# TCA_CLK_DIST_V2_4.net
KiCad netlist of a schematic drawn in Altium Designer
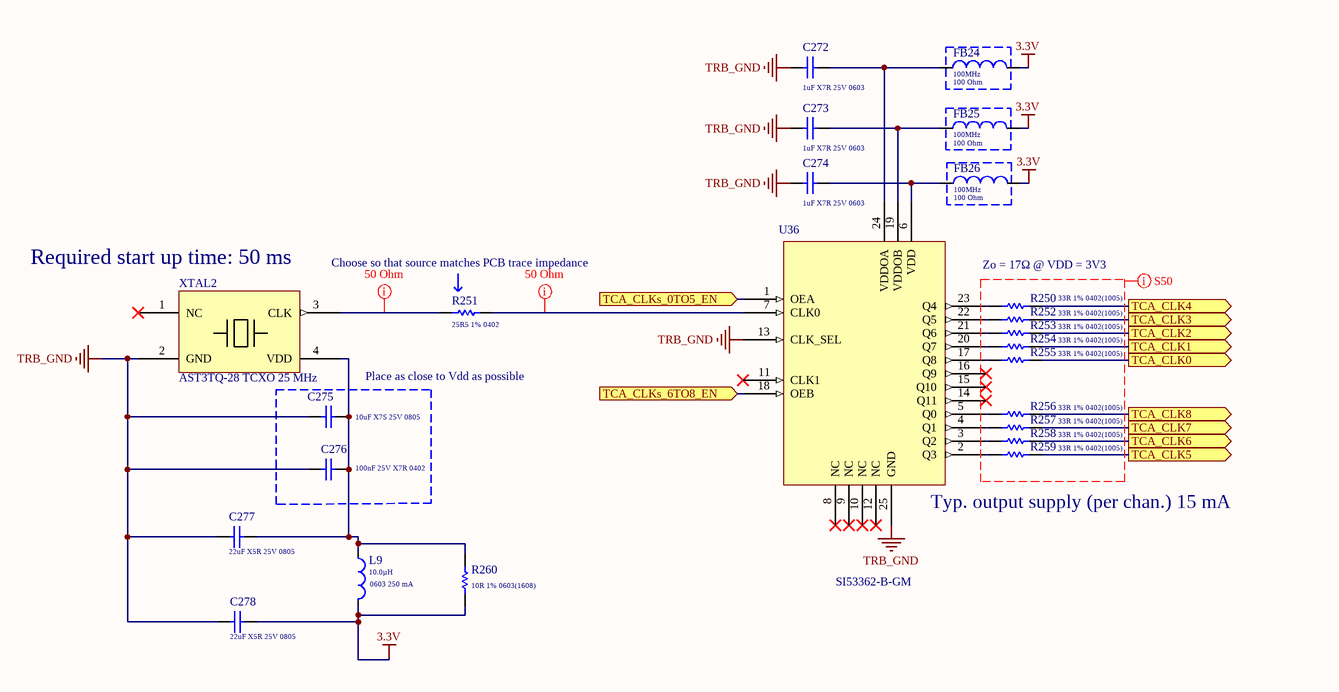
[diagram p0: TCA_CLK_DIST_V2_4.SchDoc]

(export (version "E")
  (design (tool "Eeschema 10.0.6"))
  (components
    (comp (ref "C272")
      (value "Cap_Murata_GCJ188R71E105KA01J_1uF")
      (footprint "Cap_Murata_GCJ188R71E105KA01J_1uF")
      (description "CAP CER 1uF 25V X7R 0603")
      (fields (field (name "CAPACITANCE") "1uF X7R 25V 0603"))
      (libsource (lib "Cap_Murata_GCJ188R71E105KA01J_1uF") (part "Cap_Murata_GCJ188R71E105KA01J_1uF"))
    )
    (comp (ref "C273")
      (value "Cap_Murata_GCJ188R71E105KA01J_1uF")
      (footprint "Cap_Murata_GCJ188R71E105KA01J_1uF")
      (description "CAP CER 1uF 25V X7R 0603")
      (fields (field (name "CAPACITANCE") "1uF X7R 25V 0603"))
      (libsource (lib "Cap_Murata_GCJ188R71E105KA01J_1uF") (part "Cap_Murata_GCJ188R71E105KA01J_1uF"))
    )
    (comp (ref "C274")
      (value "Cap_Murata_GCJ188R71E105KA01J_1uF")
      (footprint "Cap_Murata_GCJ188R71E105KA01J_1uF")
      (description "CAP CER 1uF 25V X7R 0603")
      (fields (field (name "CAPACITANCE") "1uF X7R 25V 0603"))
      (libsource (lib "Cap_Murata_GCJ188R71E105KA01J_1uF") (part "Cap_Murata_GCJ188R71E105KA01J_1uF"))
    )
    (comp (ref "C275")
      (value "Cap_Murata_ GRM21BC71E106ME11L_10uF")
      (footprint "Cap_Murata_ GRM21BC71E106ME11L_10uF")
      (description "CAP CER 10uF 25V X7R 0805")
      (fields (field (name "CAPACITANCE") "10uF X7S 25V 0805"))
      (libsource (lib "Cap_Murata_ GRM21BC71E106ME11L_10uF") (part "Cap_Murata_ GRM21BC71E106ME11L_10uF"))
    )
    (comp (ref "C276")
      (value "Cap_Taiyo_Yuden_TMK105B7104KV-FR_100nF")
      (footprint "Cap_Taiyo_Yuden_TMK105B7104KV-FR_100nF")
      (description "CAP CER 100nF 25V X7R 0402")
      (fields (field (name "CAPACITANCE") "100nF 25V X7R 0402"))
      (libsource (lib "Cap_Taiyo_Yuden_TMK105B7104KV-FR_100nF") (part "Cap_Taiyo_Yuden_TMK105B7104KV-FR_100nF"))
    )
    (comp (ref "C277")
      (value "Cap_Murata_GRT21BR61E226ME13L_22uF")
      (footprint "Cap_Murata_GRT21BR61E226ME13L_22uF")
      (description "CAP CER 22uF 25V X5R 0805")
      (fields (field (name "CAPACITANCE") "22uF X5R 25V 0805"))
      (libsource (lib "Cap_Murata_GRT21BR61E226ME13L_22uF") (part "Cap_Murata_GRT21BR61E226ME13L_22uF"))
    )
    (comp (ref "C278")
      (value "Cap_Murata_GRT21BR61E226ME13L_22uF")
      (footprint "Cap_Murata_GRT21BR61E226ME13L_22uF")
      (description "CAP CER 22uF 25V X5R 0805")
      (fields (field (name "CAPACITANCE") "22uF X5R 25V 0805"))
      (libsource (lib "Cap_Murata_GRT21BR61E226ME13L_22uF") (part "Cap_Murata_GRT21BR61E226ME13L_22uF"))
    )
    (comp (ref "FB24")
      (value "742792731")
      (footprint "FB_Wurth_Electronics_742792731_100Ohms")
      (description "FB SMD 100 OHM 25% 1.2A 0402")
      (fields (field (name "MEASURING FREQUENCY") "100MHz") (field (name "IMPEDANCE") "100 Ohm"))
      (libsource (lib "FB_Wurth_Electronics_742792731_100Ohms") (part "FB_Wurth_Electronics_742792731_100Ohms"))
    )
    (comp (ref "FB25")
      (value "742792731")
      (footprint "FB_Wurth_Electronics_742792731_100Ohms")
      (description "FB SMD 100 OHM 25% 1.2A 0402")
      (fields (field (name "MEASURING FREQUENCY") "100MHz") (field (name "IMPEDANCE") "100 Ohm"))
      (libsource (lib "FB_Wurth_Electronics_742792731_100Ohms") (part "FB_Wurth_Electronics_742792731_100Ohms"))
    )
    (comp (ref "FB26")
      (value "742792731")
      (footprint "FB_Wurth_Electronics_742792731_100Ohms")
      (description "FB SMD 100 OHM 25% 1.2A 0402")
      (fields (field (name "MEASURING FREQUENCY") "100MHz") (field (name "IMPEDANCE") "100 Ohm"))
      (libsource (lib "FB_Wurth_Electronics_742792731_100Ohms") (part "FB_Wurth_Electronics_742792731_100Ohms"))
    )
    (comp (ref "L9")
      (value "0603 250 mA")
      (footprint "TDK_MLZ1608M100WT_0")
      (description "IND 10µH Shielded Multilayer Inductor 250mA 1.365 Ohm Max 0603 (1608 Metric)")
      (fields
        (field (name "PART NUMBER") "MLZ1608M100WT")
        (field (name "MANUFACTURER") "TDK")
        (field (name "INDUCTANCE") "10.0µH")
      )
      (libsource (lib "Ind_TDK_MLZ1608M100WT_10uH") (part "Ind_TDK_MLZ1608M100WT_eec"))
    )
    (comp (ref "R250")
      (value "33R 1% 0402(1005)")
      (footprint "RESC0402(1005)_L")
      (description "33R 0.063W 1% 0402 (1005 Metric)  SMD")
      (fields (field (name "TOLERANCE") "1 %") (field (name "POWER") "0.063 W"))
      (libsource (lib "Altium Content Vault") (part "RES"))
    )
    (comp (ref "R251")
      (value "25R5 1% 0402")
      (footprint "RESC0402(1005)_L")
      (description "25R5 0.063W 1% 0402 (1005 Metric)  SMD")
      (fields (field (name "TOLERANCE") "1 %") (field (name "POWER") "0.063 W"))
      (libsource (lib "Altium Content Vault") (part "RES"))
    )
    (comp (ref "R252")
      (value "33R 1% 0402(1005)")
      (footprint "RESC0402(1005)_L")
      (description "33R 0.063W 1% 0402 (1005 Metric)  SMD")
      (fields (field (name "TOLERANCE") "1 %") (field (name "POWER") "0.063 W"))
      (libsource (lib "Altium Content Vault") (part "RES"))
    )
    (comp (ref "R253")
      (value "33R 1% 0402(1005)")
      (footprint "RESC0402(1005)_L")
      (description "33R 0.063W 1% 0402 (1005 Metric)  SMD")
      (fields (field (name "TOLERANCE") "1 %") (field (name "POWER") "0.063 W"))
      (libsource (lib "Altium Content Vault") (part "RES"))
    )
    (comp (ref "R254")
      (value "33R 1% 0402(1005)")
      (footprint "RESC0402(1005)_L")
      (description "33R 0.063W 1% 0402 (1005 Metric)  SMD")
      (fields (field (name "TOLERANCE") "1 %") (field (name "POWER") "0.063 W"))
      (libsource (lib "Altium Content Vault") (part "RES"))
    )
    (comp (ref "R255")
      (value "33R 1% 0402(1005)")
      (footprint "RESC0402(1005)_L")
      (description "33R 0.063W 1% 0402 (1005 Metric)  SMD")
      (fields (field (name "TOLERANCE") "1 %") (field (name "POWER") "0.063 W"))
      (libsource (lib "Altium Content Vault") (part "RES"))
    )
    (comp (ref "R256")
      (value "33R 1% 0402(1005)")
      (footprint "RESC0402(1005)_L")
      (description "33R 0.063W 1% 0402 (1005 Metric)  SMD")
      (fields (field (name "TOLERANCE") "1 %") (field (name "POWER") "0.063 W"))
      (libsource (lib "Altium Content Vault") (part "RES"))
    )
    (comp (ref "R257")
      (value "33R 1% 0402(1005)")
      (footprint "RESC0402(1005)_L")
      (description "33R 0.063W 1% 0402 (1005 Metric)  SMD")
      (fields (field (name "TOLERANCE") "1 %") (field (name "POWER") "0.063 W"))
      (libsource (lib "Altium Content Vault") (part "RES"))
    )
    (comp (ref "R258")
      (value "33R 1% 0402(1005)")
      (footprint "RESC0402(1005)_L")
      (description "33R 0.063W 1% 0402 (1005 Metric)  SMD")
      (fields (field (name "TOLERANCE") "1 %") (field (name "POWER") "0.063 W"))
      (libsource (lib "Altium Content Vault") (part "RES"))
    )
    (comp (ref "R259")
      (value "33R 1% 0402(1005)")
      (footprint "RESC0402(1005)_L")
      (description "33R 0.063W 1% 0402 (1005 Metric)  SMD")
      (fields (field (name "TOLERANCE") "1 %") (field (name "POWER") "0.063 W"))
      (libsource (lib "Altium Content Vault") (part "RES"))
    )
    (comp (ref "R260")
      (value "10R 1% 0603(1608)")
      (footprint "RESC0603(1608)_L")
      (description "10R 0.1W 1% 0603 (1608 Metric)  SMD")
      (fields (field (name "TOLERANCE") "1 %") (field (name "POWER") "0.1 W"))
      (libsource (lib "Altium Content Vault") (part "RES"))
    )
    (comp (ref "U36")
      (value "SI53362-B-GM")
      (footprint "Si53362")
      (description "Clock Buffer LVCMOS 2:12 buffer (200MHz), 2:1 LVCMOS input max, output enable (QFN24)")
      (libsource (lib "SI53362") (part "SI53362-B-GM"))
    )
    (comp (ref "XTAL2")
      (value "AST3TQ-28 TCXO 25 MHz")
      (footprint "XTAL_ASDM1-25.000MHZ-LC-T")
      (description "TCXO Oscillators 25MHz 3.3Volt LVCMOS 0.280 ppm -40C 85C")
      (libsource (lib "XTAL_Abracaon_AST3TQ-T-25.000MHz-28") (part "AST3TQ-28"))
    )
  )
  (nets
    (net (code "1") (name "/TCA_CLK0") (class "Default")
      (node (ref "R255") (pin "2") (pinfunction "2_2") (pintype "passive"))
    )
    (net (code "2") (name "/TCA_CLK1") (class "Default")
      (node (ref "R254") (pin "2") (pinfunction "2_2") (pintype "passive"))
    )
    (net (code "3") (name "/TCA_CLK2") (class "Default")
      (node (ref "R253") (pin "2") (pinfunction "2_2") (pintype "passive"))
    )
    (net (code "4") (name "/TCA_CLK3") (class "Default")
      (node (ref "R252") (pin "2") (pinfunction "2_2") (pintype "passive"))
    )
    (net (code "5") (name "/TCA_CLK4") (class "Default")
      (node (ref "R250") (pin "2") (pinfunction "2_2") (pintype "passive"))
    )
    (net (code "6") (name "/TCA_CLK5") (class "Default")
      (node (ref "R259") (pin "2") (pinfunction "2_2") (pintype "passive"))
    )
    (net (code "7") (name "/TCA_CLK6") (class "Default")
      (node (ref "R258") (pin "2") (pinfunction "2_2") (pintype "passive"))
    )
    (net (code "8") (name "/TCA_CLK7") (class "Default")
      (node (ref "R257") (pin "2") (pinfunction "2_2") (pintype "passive"))
    )
    (net (code "9") (name "/TCA_CLK8") (class "Default")
      (node (ref "R256") (pin "2") (pinfunction "2_2") (pintype "passive"))
    )
    (net (code "10") (name "/TCA_CLKs_0TO5_EN") (class "Default")
      (node (ref "U36") (pin "1") (pinfunction "OEA_1") (pintype "input"))
    )
    (net (code "11") (name "/TCA_CLKs_6TO8_EN") (class "Default")
      (node (ref "U36") (pin "18") (pinfunction "OEB_18") (pintype "input"))
    )
    (net (code "12") (name "3.3V") (class "Default")
      (node (ref "C278") (pin "2") (pinfunction "2_2") (pintype "passive"))
      (node (ref "FB24") (pin "2") (pinfunction "2_2") (pintype "passive"))
      (node (ref "FB25") (pin "2") (pinfunction "2_2") (pintype "passive"))
      (node (ref "FB26") (pin "2") (pinfunction "2_2") (pintype "passive"))
      (node (ref "L9") (pin "2") (pinfunction "2_2") (pintype "passive"))
      (node (ref "R260") (pin "1") (pinfunction "1_1") (pintype "passive"))
    )
    (net (code "13") (name "Net-(U36-CLK0)") (class "Default")
      (node (ref "R251") (pin "2") (pinfunction "2_2") (pintype "passive"))
      (node (ref "U36") (pin "7") (pinfunction "CLK0_7") (pintype "input"))
    )
    (net (code "14") (name "Net-(U36-Q0)") (class "Default")
      (node (ref "R256") (pin "1") (pinfunction "1_1") (pintype "passive"))
      (node (ref "U36") (pin "5") (pinfunction "Q0_5") (pintype "output"))
    )
    (net (code "15") (name "Net-(U36-Q1)") (class "Default")
      (node (ref "R257") (pin "1") (pinfunction "1_1") (pintype "passive"))
      (node (ref "U36") (pin "4") (pinfunction "Q1_4") (pintype "output"))
    )
    (net (code "16") (name "Net-(U36-Q2)") (class "Default")
      (node (ref "R258") (pin "1") (pinfunction "1_1") (pintype "passive"))
      (node (ref "U36") (pin "3") (pinfunction "Q2_3") (pintype "output"))
    )
    (net (code "17") (name "Net-(U36-Q3)") (class "Default")
      (node (ref "R259") (pin "1") (pinfunction "1_1") (pintype "passive"))
      (node (ref "U36") (pin "2") (pinfunction "Q3_2") (pintype "output"))
    )
    (net (code "18") (name "Net-(U36-Q4)") (class "Default")
      (node (ref "R250") (pin "1") (pinfunction "1_1") (pintype "passive"))
      (node (ref "U36") (pin "23") (pinfunction "Q4_23") (pintype "output"))
    )
    (net (code "19") (name "Net-(U36-Q5)") (class "Default")
      (node (ref "R252") (pin "1") (pinfunction "1_1") (pintype "passive"))
      (node (ref "U36") (pin "22") (pinfunction "Q5_22") (pintype "output"))
    )
    (net (code "20") (name "Net-(U36-Q6)") (class "Default")
      (node (ref "R253") (pin "1") (pinfunction "1_1") (pintype "passive"))
      (node (ref "U36") (pin "21") (pinfunction "Q6_21") (pintype "output"))
    )
    (net (code "21") (name "Net-(U36-Q7)") (class "Default")
      (node (ref "R254") (pin "1") (pinfunction "1_1") (pintype "passive"))
      (node (ref "U36") (pin "20") (pinfunction "Q7_20") (pintype "output"))
    )
    (net (code "22") (name "Net-(U36-Q8)") (class "Default")
      (node (ref "R255") (pin "1") (pinfunction "1_1") (pintype "passive"))
      (node (ref "U36") (pin "17") (pinfunction "Q8_17") (pintype "output"))
    )
    (net (code "23") (name "Net-(U36-VDD)") (class "Default")
      (node (ref "C274") (pin "1") (pinfunction "1_1") (pintype "passive"))
      (node (ref "FB26") (pin "1") (pinfunction "1_1") (pintype "passive"))
      (node (ref "U36") (pin "6") (pinfunction "VDD_6") (pintype "power_in"))
    )
    (net (code "24") (name "Net-(U36-VDDOA)") (class "Default")
      (node (ref "C272") (pin "1") (pinfunction "1_1") (pintype "passive"))
      (node (ref "FB24") (pin "1") (pinfunction "1_1") (pintype "passive"))
      (node (ref "U36") (pin "24") (pinfunction "VDDOA_24") (pintype "power_in"))
    )
    (net (code "25") (name "Net-(U36-VDDOB)") (class "Default")
      (node (ref "C273") (pin "1") (pinfunction "1_1") (pintype "passive"))
      (node (ref "FB25") (pin "1") (pinfunction "1_1") (pintype "passive"))
      (node (ref "U36") (pin "19") (pinfunction "VDDOB_19") (pintype "power_in"))
    )
    (net (code "26") (name "Net-(XTAL2-CLK)") (class "Default")
      (node (ref "R251") (pin "1") (pinfunction "1_1") (pintype "passive"))
      (node (ref "XTAL2") (pin "3") (pinfunction "CLK_3") (pintype "output"))
    )
    (net (code "27") (name "Net-(XTAL2-VDD)") (class "Default")
      (node (ref "C275") (pin "2") (pinfunction "2_2") (pintype "passive"))
      (node (ref "C276") (pin "1") (pinfunction "1_1") (pintype "passive"))
      (node (ref "C277") (pin "2") (pinfunction "2_2") (pintype "passive"))
      (node (ref "L9") (pin "1") (pinfunction "1_1") (pintype "passive"))
      (node (ref "R260") (pin "2") (pinfunction "2_2") (pintype "passive"))
      (node (ref "XTAL2") (pin "4") (pinfunction "VDD_4") (pintype "power_in"))
    )
    (net (code "28") (name "TRB_GND") (class "Default")
      (node (ref "C272") (pin "2") (pinfunction "2_2") (pintype "passive"))
      (node (ref "C273") (pin "2") (pinfunction "2_2") (pintype "passive"))
      (node (ref "C274") (pin "2") (pinfunction "2_2") (pintype "passive"))
      (node (ref "C275") (pin "1") (pinfunction "1_1") (pintype "passive"))
      (node (ref "C276") (pin "2") (pinfunction "2_2") (pintype "passive"))
      (node (ref "C277") (pin "1") (pinfunction "1_1") (pintype "passive"))
      (node (ref "C278") (pin "1") (pinfunction "1_1") (pintype "passive"))
      (node (ref "U36") (pin "13") (pinfunction "CLK_SEL_13") (pintype "input"))
      (node (ref "U36") (pin "25") (pinfunction "GND_25") (pintype "passive"))
      (node (ref "XTAL2") (pin "2") (pinfunction "GND_2") (pintype "passive"))
    )
    (net (code "29") (name "unconnected-(U36-CLK1-Pad11)") (class "Default")
      (node (ref "U36") (pin "11") (pinfunction "CLK1_11") (pintype "input+no_connect"))
    )
    (net (code "30") (name "unconnected-(U36-NC-Pad8)") (class "Default")
      (node (ref "U36") (pin "8") (pinfunction "NC_8") (pintype "passive+no_connect"))
    )
    (net (code "31") (name "unconnected-(U36-NC-Pad9)") (class "Default")
      (node (ref "U36") (pin "9") (pinfunction "NC_9") (pintype "passive+no_connect"))
    )
    (net (code "32") (name "unconnected-(U36-NC-Pad10)") (class "Default")
      (node (ref "U36") (pin "10") (pinfunction "NC_10") (pintype "passive+no_connect"))
    )
    (net (code "33") (name "unconnected-(U36-NC-Pad12)") (class "Default")
      (node (ref "U36") (pin "12") (pinfunction "NC_12") (pintype "passive+no_connect"))
    )
    (net (code "34") (name "unconnected-(U36-Q9-Pad16)") (class "Default")
      (node (ref "U36") (pin "16") (pinfunction "Q9_16") (pintype "output+no_connect"))
    )
    (net (code "35") (name "unconnected-(U36-Q10-Pad15)") (class "Default")
      (node (ref "U36") (pin "15") (pinfunction "Q10_15") (pintype "output+no_connect"))
    )
    (net (code "36") (name "unconnected-(U36-Q11-Pad14)") (class "Default")
      (node (ref "U36") (pin "14") (pinfunction "Q11_14") (pintype "output+no_connect"))
    )
    (net (code "37") (name "unconnected-(XTAL2-NC-Pad1)") (class "Default")
      (node (ref "XTAL2") (pin "1") (pinfunction "NC_1") (pintype "passive+no_connect"))
    )
  )
)
